# PSU_LM20125_ADJ.net
KiCad netlist of a schematic drawn in Altium Designer
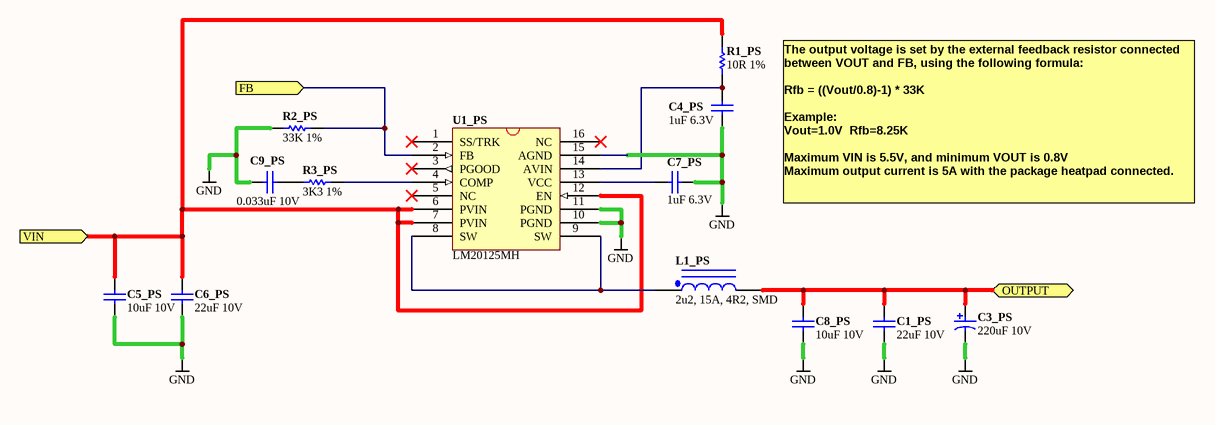
[diagram p0: PSU_LM20125_ADJ.SchDoc]

(export (version "E")
  (design (tool "Eeschema 10.0.6"))
  (components
    (comp (ref "C1_PS")
      (value "22uF 10V")
      (footprint "CAPC3225-STAR")
      (description "Capacitor, Ceramic, 22uF -20%/+80% 10V 1210 (3225) Y5V")
      (fields (field (name "TOLERANCE") "-20 / +80 %"))
      (libsource (lib "AltiumDesignLibrary") (part "CAP-NP"))
    )
    (comp (ref "C3_PS")
      (value "220uF 10V")
      (footprint "CAPC7343-STAR")
      (description "Capacitor, Tantalum, 220uF 10% 10V MCCT-D (7343-31)")
      (fields (field (name "TOLERANCE") "10 %"))
      (libsource (lib "AltiumDesignLibrary") (part "CAP-P"))
    )
    (comp (ref "C4_PS")
      (value "1uF 6.3V")
      (footprint "CAPC1005-STAR")
      (description "Capacitor, Ceramic, 1uF 10% 6.3V 0402 (1005) X5R")
      (fields (field (name "TOLERANCE") "10 %"))
      (libsource (lib "AltiumDesignLibrary") (part "CAP-NP"))
    )
    (comp (ref "C5_PS")
      (value "10uF 10V")
      (footprint "CAPC2012-STAR")
      (description "Capacitor, Ceramic, 10uF 10% 10V 0805 (2012) X5R")
      (fields (field (name "TOLERANCE") "10 %"))
      (libsource (lib "AltiumDesignLibrary") (part "CAP-NP"))
    )
    (comp (ref "C6_PS")
      (value "22uF 10V")
      (footprint "CAPC3225-STAR")
      (description "Capacitor, Ceramic, 22uF -20%/+80% 10V 1210 (3225) Y5V")
      (fields (field (name "TOLERANCE") "-20 / +80 %"))
      (libsource (lib "AltiumDesignLibrary") (part "CAP-NP"))
    )
    (comp (ref "C7_PS")
      (value "1uF 6.3V")
      (footprint "CAPC1005-STAR")
      (description "Capacitor, Ceramic, 1uF 10% 6.3V 0402 (1005) X5R")
      (fields (field (name "TOLERANCE") "10 %"))
      (libsource (lib "AltiumDesignLibrary") (part "CAP-NP"))
    )
    (comp (ref "C8_PS")
      (value "10uF 10V")
      (footprint "CAPC2012-STAR")
      (description "Capacitor, Ceramic, 10uF 10% 10V 0805 (2012) X5R")
      (fields (field (name "TOLERANCE") "10 %"))
      (libsource (lib "AltiumDesignLibrary") (part "CAP-NP"))
    )
    (comp (ref "C9_PS")
      (value "0.033uF 10V")
      (footprint "CAPC1005-STAR")
      (description "Capacitor, Ceramic, 0.033uF 10% 10V 0402 (1005) X7R")
      (fields (field (name "TOLERANCE") "10 %"))
      (libsource (lib "AltiumDesignLibrary") (part "CAP-NP"))
    )
    (comp (ref "L1_PS")
      (value "2u2, 15A, 4R2, SMD")
      (footprint "IND-EPCOS-SMD-B82559")
      (description "Inductor, 2.2uH, 15A, 4R2, SMD")
      (libsource (lib "AltiumDesignLibrary") (part "IND-IRON-DOT"))
    )
    (comp (ref "R1_PS")
      (value "10R 1%")
      (footprint "RESC1005-STAR")
      (description "Resistor, 10R 1% 0402 (1005)")
      (fields (field (name "TOLERANCE") "1 %"))
      (libsource (lib "AltiumDesignLibrary") (part "RES"))
    )
    (comp (ref "R2_PS")
      (value "33K 1%")
      (footprint "RESC1005-STAR")
      (description "Resistor, 33K 1% 0402 (1005)")
      (fields (field (name "TOLERANCE") "1 %"))
      (libsource (lib "AltiumDesignLibrary") (part "RES"))
    )
    (comp (ref "R3_PS")
      (value "3K3 1%")
      (footprint "RESC1005-STAR")
      (description "Resistor, 3K3 1% 0402 (1005)")
      (fields (field (name "TOLERANCE") "1 %"))
      (libsource (lib "AltiumDesignLibrary") (part "RES"))
    )
    (comp (ref "U1_PS")
      (value "LM20125MH")
      (footprint "TSOP65P638-16")
      (description "LM20125MH, 5A, Synchronous Buck Regulator")
      (libsource (lib "AltiumDesignLibrary") (part "LM20125"))
    )
  )
  (nets
    (net (code "1") (name "/FB") (class "Default")
      (node (ref "R2_PS") (pin "2") (pinfunction "2_2") (pintype "passive"))
      (node (ref "U1_PS") (pin "2") (pinfunction "FB_2") (pintype "input"))
    )
    (net (code "2") (name "/OUTPUT") (class "Default")
      (node (ref "C1_PS") (pin "1") (pinfunction "1_1") (pintype "passive"))
      (node (ref "C3_PS") (pin "1") (pinfunction "1_1") (pintype "passive"))
      (node (ref "C8_PS") (pin "1") (pinfunction "1_1") (pintype "passive"))
      (node (ref "L1_PS") (pin "2") (pinfunction "2_2") (pintype "passive"))
    )
    (net (code "3") (name "/VIN") (class "Default")
      (node (ref "C5_PS") (pin "1") (pinfunction "1_1") (pintype "passive"))
      (node (ref "C6_PS") (pin "1") (pinfunction "1_1") (pintype "passive"))
      (node (ref "R1_PS") (pin "1") (pinfunction "1_1") (pintype "passive"))
      (node (ref "U1_PS") (pin "12") (pinfunction "EN_12") (pintype "input"))
      (node (ref "U1_PS") (pin "6") (pinfunction "PVIN_6") (pintype "passive"))
      (node (ref "U1_PS") (pin "7") (pinfunction "PVIN_7") (pintype "passive"))
    )
    (net (code "4") (name "GND") (class "Default")
      (node (ref "C1_PS") (pin "2") (pinfunction "2_2") (pintype "passive"))
      (node (ref "C3_PS") (pin "2") (pinfunction "2_2") (pintype "passive"))
      (node (ref "C4_PS") (pin "2") (pinfunction "2_2") (pintype "passive"))
      (node (ref "C5_PS") (pin "2") (pinfunction "2_2") (pintype "passive"))
      (node (ref "C6_PS") (pin "2") (pinfunction "2_2") (pintype "passive"))
      (node (ref "C7_PS") (pin "2") (pinfunction "2_2") (pintype "passive"))
      (node (ref "C8_PS") (pin "2") (pinfunction "2_2") (pintype "passive"))
      (node (ref "C9_PS") (pin "1") (pinfunction "1_1") (pintype "passive"))
      (node (ref "R2_PS") (pin "1") (pinfunction "1_1") (pintype "passive"))
      (node (ref "U1_PS") (pin "10") (pinfunction "PGND_10") (pintype "power_in"))
      (node (ref "U1_PS") (pin "11") (pinfunction "PGND_11") (pintype "power_in"))
      (node (ref "U1_PS") (pin "15") (pinfunction "AGND_15") (pintype "passive"))
    )
    (net (code "5") (name "Net-(C9_PS-Pad2)") (class "Default")
      (node (ref "C9_PS") (pin "2") (pinfunction "2_2") (pintype "passive"))
      (node (ref "R3_PS") (pin "1") (pinfunction "1_1") (pintype "passive"))
    )
    (net (code "6") (name "Net-(L1_PS-Pad1)") (class "Default")
      (node (ref "L1_PS") (pin "1") (pinfunction "1_1") (pintype "passive"))
      (node (ref "U1_PS") (pin "8") (pinfunction "SW_8") (pintype "passive"))
      (node (ref "U1_PS") (pin "9") (pinfunction "SW_9") (pintype "passive"))
    )
    (net (code "7") (name "Net-(U1_PS-AVIN)") (class "Default")
      (node (ref "C4_PS") (pin "1") (pinfunction "1_1") (pintype "passive"))
      (node (ref "R1_PS") (pin "2") (pinfunction "2_2") (pintype "passive"))
      (node (ref "U1_PS") (pin "14") (pinfunction "AVIN_14") (pintype "passive"))
    )
    (net (code "8") (name "Net-(U1_PS-COMP)") (class "Default")
      (node (ref "R3_PS") (pin "2") (pinfunction "2_2") (pintype "passive"))
      (node (ref "U1_PS") (pin "4") (pinfunction "COMP_4") (pintype "input"))
    )
    (net (code "9") (name "Net-(U1_PS-VCC)") (class "Default")
      (node (ref "C7_PS") (pin "1") (pinfunction "1_1") (pintype "passive"))
      (node (ref "U1_PS") (pin "13") (pinfunction "VCC_13") (pintype "passive"))
    )
    (net (code "10") (name "unconnected-(U1_PS-NC-Pad5)") (class "Default")
      (node (ref "U1_PS") (pin "5") (pinfunction "NC_5") (pintype "passive+no_connect"))
    )
    (net (code "11") (name "unconnected-(U1_PS-NC-Pad16)") (class "Default")
      (node (ref "U1_PS") (pin "16") (pinfunction "NC_16") (pintype "passive+no_connect"))
    )
    (net (code "12") (name "unconnected-(U1_PS-PGOOD-Pad3)") (class "Default")
      (node (ref "U1_PS") (pin "3") (pinfunction "PGOOD_3") (pintype "output+no_connect"))
    )
    (net (code "13") (name "unconnected-(U1_PS-SS{slash}TRK-Pad1)") (class "Default")
      (node (ref "U1_PS") (pin "1") (pinfunction "SS/TRK_1") (pintype "passive+no_connect"))
    )
  )
)
